# uC_Alimentacion.net
KiCad netlist of a schematic drawn in Altium Designer
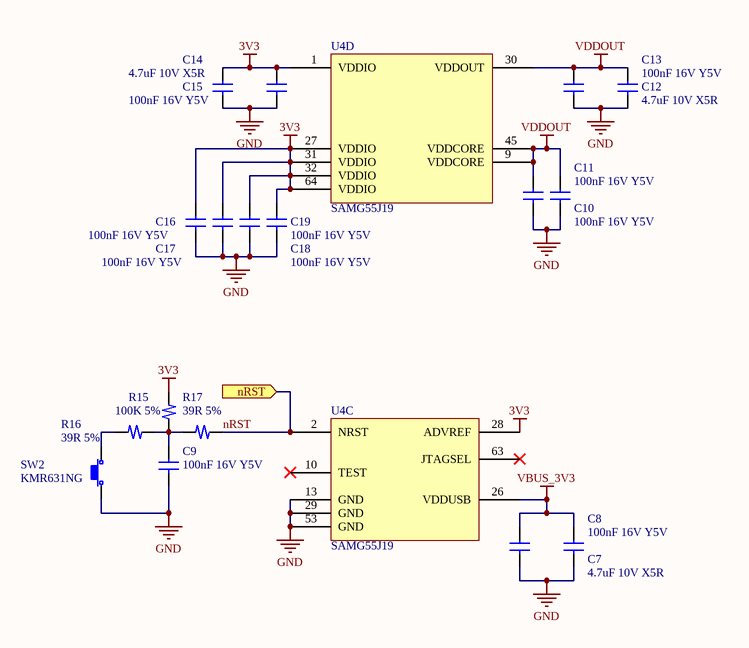
[diagram p0: uC_Alimentacion.SchDoc]

(export (version "E")
  (design (tool "Eeschema 10.0.6"))
  (components
    (comp (ref "C7")
      (value "4.7uF 10V X5R")
      (footprint "C_0402")
      (description "Ceramic Capacitor SMD 0402")
      (libsource (lib "Oxy_Lib") (part "Ceramic Capacitor"))
    )
    (comp (ref "C8")
      (value "100nF 16V Y5V")
      (footprint "C_0402")
      (description "Ceramic Capacitor SMD 0402")
      (libsource (lib "Oxy_Lib") (part "Ceramic Capacitor"))
    )
    (comp (ref "C9")
      (value "100nF 16V Y5V")
      (footprint "C_0402")
      (description "Ceramic Capacitor SMD 0402")
      (libsource (lib "Oxy_Lib") (part "Ceramic Capacitor"))
    )
    (comp (ref "C10")
      (value "100nF 16V Y5V")
      (footprint "C_0402")
      (description "Ceramic Capacitor SMD 0402")
      (libsource (lib "Oxy_Lib") (part "Ceramic Capacitor"))
    )
    (comp (ref "C11")
      (value "100nF 16V Y5V")
      (footprint "C_0402")
      (description "Ceramic Capacitor SMD 0402")
      (libsource (lib "Oxy_Lib") (part "Ceramic Capacitor"))
    )
    (comp (ref "C12")
      (value "4.7uF 10V X5R")
      (footprint "C_0402")
      (description "Ceramic Capacitor SMD 0402")
      (libsource (lib "Oxy_Lib") (part "Ceramic Capacitor"))
    )
    (comp (ref "C13")
      (value "100nF 16V Y5V")
      (footprint "C_0402")
      (description "Ceramic Capacitor SMD 0402")
      (libsource (lib "Oxy_Lib") (part "Ceramic Capacitor"))
    )
    (comp (ref "C14")
      (value "4.7uF 10V X5R")
      (footprint "C_0402")
      (description "Ceramic Capacitor SMD 0402")
      (libsource (lib "Oxy_Lib") (part "Ceramic Capacitor"))
    )
    (comp (ref "C15")
      (value "100nF 16V Y5V")
      (footprint "C_0402")
      (description "Ceramic Capacitor SMD 0402")
      (libsource (lib "Oxy_Lib") (part "Ceramic Capacitor"))
    )
    (comp (ref "C16")
      (value "100nF 16V Y5V")
      (footprint "C_0402")
      (description "Ceramic Capacitor SMD 0402")
      (libsource (lib "Oxy_Lib") (part "Ceramic Capacitor"))
    )
    (comp (ref "C17")
      (value "100nF 16V Y5V")
      (footprint "C_0402")
      (description "Ceramic Capacitor SMD 0402")
      (libsource (lib "Oxy_Lib") (part "Ceramic Capacitor"))
    )
    (comp (ref "C18")
      (value "100nF 16V Y5V")
      (footprint "C_0402")
      (description "Ceramic Capacitor SMD 0402")
      (libsource (lib "Oxy_Lib") (part "Ceramic Capacitor"))
    )
    (comp (ref "C19")
      (value "100nF 16V Y5V")
      (footprint "C_0402")
      (description "Ceramic Capacitor SMD 0402")
      (libsource (lib "Oxy_Lib") (part "Ceramic Capacitor"))
    )
    (comp (ref "R15")
      (value "100K 5%")
      (footprint "R_0402")
      (description "Resistor SMD 0402")
      (libsource (lib "Oxy_Lib") (part "Resistor"))
    )
    (comp (ref "R16")
      (value "39R 5%")
      (footprint "R_0402")
      (description "Resistor SMD 0402")
      (libsource (lib "Oxy_Lib") (part "Resistor"))
    )
    (comp (ref "R17")
      (value "39R 5%")
      (footprint "R_0402")
      (description "Resistor SMD 0402")
      (libsource (lib "Oxy_Lib") (part "Resistor"))
    )
    (comp (ref "SW2")
      (value "KMR631NG")
      (footprint "TACT SWITCH")
      (description "Tact Switch")
      (libsource (lib "Oxy_Lib") (part "Tact Switch"))
    )
    (comp (ref "U4")
      (value "SAMG55J19")
      (footprint "LQFP 64")
      (description "Atmel SMART SAM G55 Cortex M4 32-bit 64-lead LQFP")
      (libsource (lib "Oxy_Lib") (part "SAMG55J19"))
    )
  )
  (nets
    (net (code "1") (name "/nRST") (class "Default")
      (node (ref "R17") (pin "2") (pinfunction "2_2") (pintype "passive"))
      (node (ref "U4") (pin "2") (pinfunction "NRST_2") (pintype "passive"))
    )
    (net (code "2") (name "3V3") (class "Default")
      (node (ref "C14") (pin "1") (pinfunction "1_1") (pintype "passive"))
      (node (ref "C15") (pin "1") (pinfunction "1_1") (pintype "passive"))
      (node (ref "C16") (pin "1") (pinfunction "1_1") (pintype "passive"))
      (node (ref "C17") (pin "1") (pinfunction "1_1") (pintype "passive"))
      (node (ref "C18") (pin "1") (pinfunction "1_1") (pintype "passive"))
      (node (ref "C19") (pin "1") (pinfunction "1_1") (pintype "passive"))
      (node (ref "R15") (pin "2") (pinfunction "2_2") (pintype "passive"))
      (node (ref "U4") (pin "1") (pinfunction "VDDIO_1") (pintype "passive"))
      (node (ref "U4") (pin "27") (pinfunction "VDDIO_27") (pintype "passive"))
      (node (ref "U4") (pin "28") (pinfunction "ADVREF_28") (pintype "passive"))
      (node (ref "U4") (pin "31") (pinfunction "VDDIO_31") (pintype "passive"))
      (node (ref "U4") (pin "32") (pinfunction "VDDIO_32") (pintype "passive"))
      (node (ref "U4") (pin "64") (pinfunction "VDDIO_64") (pintype "passive"))
    )
    (net (code "3") (name "GND") (class "Default")
      (node (ref "C10") (pin "2") (pinfunction "2_2") (pintype "passive"))
      (node (ref "C11") (pin "2") (pinfunction "2_2") (pintype "passive"))
      (node (ref "C12") (pin "2") (pinfunction "2_2") (pintype "passive"))
      (node (ref "C13") (pin "2") (pinfunction "2_2") (pintype "passive"))
      (node (ref "C14") (pin "2") (pinfunction "2_2") (pintype "passive"))
      (node (ref "C15") (pin "2") (pinfunction "2_2") (pintype "passive"))
      (node (ref "C16") (pin "2") (pinfunction "2_2") (pintype "passive"))
      (node (ref "C17") (pin "2") (pinfunction "2_2") (pintype "passive"))
      (node (ref "C18") (pin "2") (pinfunction "2_2") (pintype "passive"))
      (node (ref "C19") (pin "2") (pinfunction "2_2") (pintype "passive"))
      (node (ref "C7") (pin "2") (pinfunction "2_2") (pintype "passive"))
      (node (ref "C8") (pin "2") (pinfunction "2_2") (pintype "passive"))
      (node (ref "C9") (pin "2") (pinfunction "2_2") (pintype "passive"))
      (node (ref "SW2") (pin "1") (pinfunction "1_1") (pintype "passive"))
      (node (ref "U4") (pin "13") (pinfunction "GND_13") (pintype "passive"))
      (node (ref "U4") (pin "29") (pinfunction "GND_29") (pintype "passive"))
      (node (ref "U4") (pin "53") (pinfunction "GND_53") (pintype "passive"))
    )
    (net (code "4") (name "Net-(C9-Pad1)") (class "Default")
      (node (ref "C9") (pin "1") (pinfunction "1_1") (pintype "passive"))
      (node (ref "R15") (pin "1") (pinfunction "1_1") (pintype "passive"))
      (node (ref "R16") (pin "2") (pinfunction "2_2") (pintype "passive"))
      (node (ref "R17") (pin "1") (pinfunction "1_1") (pintype "passive"))
    )
    (net (code "5") (name "Net-(R16-Pad1)") (class "Default")
      (node (ref "R16") (pin "1") (pinfunction "1_1") (pintype "passive"))
      (node (ref "SW2") (pin "2") (pinfunction "2_2") (pintype "passive"))
    )
    (net (code "6") (name "VBUS_3V3") (class "Default")
      (node (ref "C7") (pin "1") (pinfunction "1_1") (pintype "passive"))
      (node (ref "C8") (pin "1") (pinfunction "1_1") (pintype "passive"))
      (node (ref "U4") (pin "26") (pinfunction "VDDUSB_26") (pintype "passive"))
    )
    (net (code "7") (name "VDDOUT") (class "Default")
      (node (ref "C10") (pin "1") (pinfunction "1_1") (pintype "passive"))
      (node (ref "C11") (pin "1") (pinfunction "1_1") (pintype "passive"))
      (node (ref "C12") (pin "1") (pinfunction "1_1") (pintype "passive"))
      (node (ref "C13") (pin "1") (pinfunction "1_1") (pintype "passive"))
      (node (ref "U4") (pin "30") (pinfunction "VDDOUT_30") (pintype "passive"))
      (node (ref "U4") (pin "45") (pinfunction "VDDCORE_45") (pintype "passive"))
      (node (ref "U4") (pin "9") (pinfunction "VDDCORE_9") (pintype "passive"))
    )
    (net (code "8") (name "unconnected-(U4C-JTAGSEL-Pad63)") (class "Default")
      (node (ref "U4") (pin "63") (pinfunction "JTAGSEL_63") (pintype "passive+no_connect"))
    )
    (net (code "9") (name "unconnected-(U4C-TEST-Pad10)") (class "Default")
      (node (ref "U4") (pin "10") (pinfunction "TEST_10") (pintype "passive+no_connect"))
    )
  )
)
